# DHJSNoiseConsole.net
KiCad netlist of a schematic drawn in EAGLE
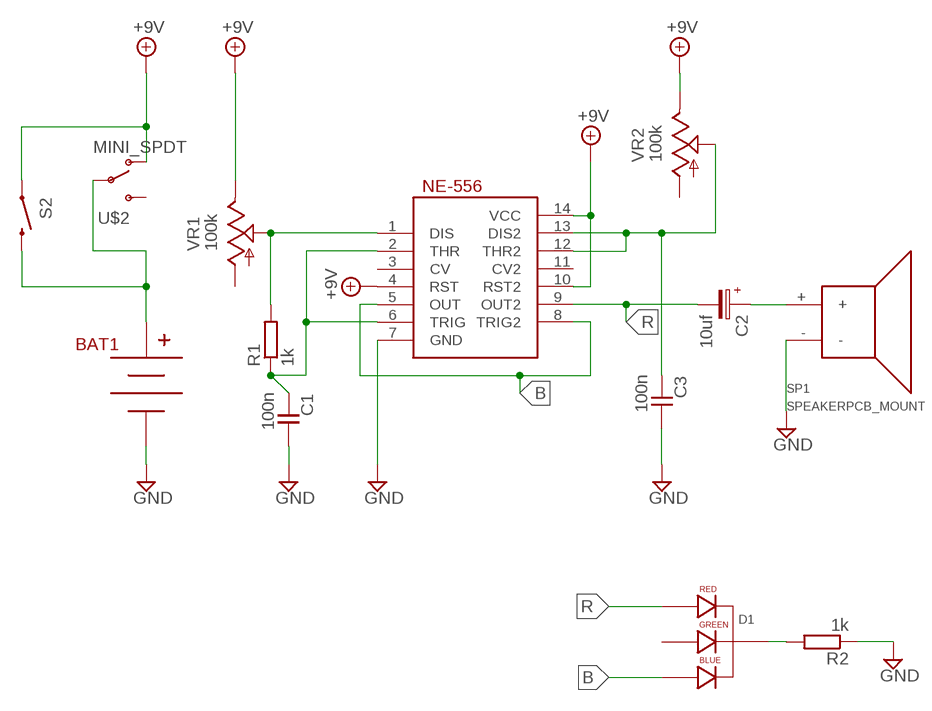
[diagram p0: schematic, sheet 1]

(export (version "E")
  (design (tool "Eeschema 10.0.6"))
  (components
    (comp (ref "BAT1")
      (value "BC9VPC")
      (footprint "eagle-import:BC9VPC")
      (libsource (lib "eagle-import") (part "BC9VPC"))
    )
    (comp (ref "C1")
      (value "100n")
      (footprint "eagle-import:C050-024X044")
      (libsource (lib "eagle-import") (part "C-EU050-024X044"))
    )
    (comp (ref "C2")
      (value "10uf")
      (footprint "eagle-import:050_020")
      (libsource (lib "eagle-import") (part "050-EU"))
    )
    (comp (ref "C3")
      (value "100n")
      (footprint "eagle-import:C050-024X044")
      (libsource (lib "eagle-import") (part "C-EU050-024X044"))
    )
    (comp (ref "D1")
      (value "LED-RGB-CC-THRUCLEAR")
      (footprint "eagle-import:LED-RGB-THRU")
      (libsource (lib "eagle-import") (part "LED-RGB-CC-THRUCLEAR"))
    )
    (comp (ref "NE-556")
      (value "556")
      (footprint "eagle-import:DIL14")
      (libsource (lib "eagle-import") (part "556"))
    )
    (comp (ref "R1")
      (value "1k")
      (footprint "eagle-import:10MM_RESISTOR")
      (libsource (lib "eagle-import") (part "RESISTOR10MM_RESISTOR"))
    )
    (comp (ref "R2")
      (value "1k")
      (footprint "eagle-import:10MM_RESISTOR")
      (libsource (lib "eagle-import") (part "RESISTOR10MM_RESISTOR"))
    )
    (comp (ref "S2")
      (value "SWITCH-MOMENTARY-2SIDE_EZ")
      (footprint "eagle-import:TACTILE-PTH-SIDEEZ")
      (libsource (lib "eagle-import") (part "SWITCH-MOMENTARY-2SIDE_EZ"))
    )
    (comp (ref "SP1")
      (value "SPEAKERPCB_MOUNT")
      (footprint "eagle-import:PCB_MOUNT_SPEAKER")
      (fields (field (name "MFG") "SANCO"))
      (libsource (lib "eagle-import") (part "SPEAKERPCB_MOUNT"))
    )
    (comp (ref "U$2")
      (value "MINI_SPDT")
      (footprint "eagle-import:MINI_SPDT_RIGHTANGLE")
      (libsource (lib "eagle-import") (part "MINI_SPDT"))
    )
    (comp (ref "VR1")
      (value "100k")
      (footprint "eagle-import:9MM_SNAP-IN_POT")
      (libsource (lib "eagle-import") (part "9MM_SNAP-IN_POT_"))
    )
    (comp (ref "VR2")
      (value "100k")
      (footprint "eagle-import:9MM_SNAP-IN_POT")
      (libsource (lib "eagle-import") (part "9MM_SNAP-IN_POT_"))
    )
  )
  (nets
    (net (code "1") (name "+9V") (class "Default")
      (node (ref "NE-556") (pin "10") (pinfunction "RST2_10") (pintype "bidirectional"))
      (node (ref "NE-556") (pin "14") (pinfunction "VCC_14") (pintype "bidirectional"))
      (node (ref "NE-556") (pin "4") (pinfunction "RST_4") (pintype "bidirectional"))
      (node (ref "S2") (pin "1") (pinfunction "1_1") (pintype "passive"))
      (node (ref "U$2") (pin "UP") (pinfunction "O_UP") (pintype "passive"))
      (node (ref "VR1") (pin "3") (pinfunction "E_3") (pintype "passive"))
      (node (ref "VR2") (pin "3") (pinfunction "E_3") (pintype "passive"))
    )
    (net (code "2") (name "B") (class "Default")
      (node (ref "D1") (pin "4") (pinfunction "BLUE_CATHODE_4") (pintype "bidirectional"))
      (node (ref "NE-556") (pin "5") (pinfunction "OUT_5") (pintype "bidirectional"))
      (node (ref "NE-556") (pin "8") (pinfunction "TRIG2_8") (pintype "bidirectional"))
    )
    (net (code "3") (name "GND") (class "Default")
      (node (ref "BAT1") (pin "V-") (pinfunction "V-_V-") (pintype "bidirectional"))
      (node (ref "C1") (pin "1") (pinfunction "1_1") (pintype "passive"))
      (node (ref "C3") (pin "1") (pinfunction "1_1") (pintype "passive"))
      (node (ref "NE-556") (pin "7") (pinfunction "GND_7") (pintype "bidirectional"))
      (node (ref "R2") (pin "1") (pinfunction "1_1") (pintype "passive"))
      (node (ref "SP1") (pin "-") (pinfunction "-_-") (pintype "bidirectional"))
    )
    (net (code "4") (name "Net-(BAT1-PadV+)") (class "Default")
      (node (ref "BAT1") (pin "V+") (pinfunction "V+_V+") (pintype "bidirectional"))
      (node (ref "S2") (pin "2") (pinfunction "2_2") (pintype "passive"))
      (node (ref "U$2") (pin "COMMON") (pinfunction "COMMON_COMMON") (pintype "passive"))
    )
    (net (code "5") (name "Net-(C2-Pad+)") (class "Default")
      (node (ref "C2") (pin "+") (pinfunction "+_+") (pintype "passive"))
      (node (ref "SP1") (pin "+") (pinfunction "+_+") (pintype "bidirectional"))
    )
    (net (code "6") (name "Net-(D1-CATHODE)") (class "Default")
      (node (ref "D1") (pin "2") (pinfunction "CATHODE_2") (pintype "bidirectional"))
      (node (ref "R2") (pin "2") (pinfunction "2_2") (pintype "passive"))
    )
    (net (code "7") (name "Net-(NE-556-DIS)") (class "Default")
      (node (ref "NE-556") (pin "1") (pinfunction "DIS_1") (pintype "bidirectional"))
      (node (ref "R1") (pin "2") (pinfunction "2_2") (pintype "passive"))
      (node (ref "VR1") (pin "2") (pinfunction "S_2") (pintype "passive"))
    )
    (net (code "8") (name "Net-(NE-556-DIS2)") (class "Default")
      (node (ref "C3") (pin "2") (pinfunction "2_2") (pintype "passive"))
      (node (ref "NE-556") (pin "12") (pinfunction "THR2_12") (pintype "bidirectional"))
      (node (ref "NE-556") (pin "13") (pinfunction "DIS2_13") (pintype "bidirectional"))
      (node (ref "VR2") (pin "2") (pinfunction "S_2") (pintype "passive"))
    )
    (net (code "9") (name "Net-(NE-556-THR)") (class "Default")
      (node (ref "C1") (pin "2") (pinfunction "2_2") (pintype "passive"))
      (node (ref "NE-556") (pin "2") (pinfunction "THR_2") (pintype "bidirectional"))
      (node (ref "NE-556") (pin "6") (pinfunction "TRIG_6") (pintype "bidirectional"))
      (node (ref "R1") (pin "1") (pinfunction "1_1") (pintype "passive"))
    )
    (net (code "10") (name "R") (class "Default")
      (node (ref "C2") (pin "-") (pinfunction "-_-") (pintype "passive"))
      (node (ref "D1") (pin "1") (pinfunction "RED_CATHODE_1") (pintype "bidirectional"))
      (node (ref "NE-556") (pin "9") (pinfunction "OUT2_9") (pintype "bidirectional"))
    )
    (net (code "11") (name "unconnected-(D1-GREEN_CATHODE-Pad3)") (class "Default")
      (node (ref "D1") (pin "3") (pinfunction "GREEN_CATHODE_3") (pintype "bidirectional"))
    )
    (net (code "12") (name "unconnected-(NE-556-CV-Pad3)") (class "Default")
      (node (ref "NE-556") (pin "3") (pinfunction "CV_3") (pintype "bidirectional"))
    )
    (net (code "13") (name "unconnected-(NE-556-CV2-Pad11)") (class "Default")
      (node (ref "NE-556") (pin "11") (pinfunction "CV2_11") (pintype "bidirectional"))
    )
    (net (code "14") (name "unconnected-(U$2-S-PadDOWN)") (class "Default")
      (node (ref "U$2") (pin "DOWN") (pinfunction "S_DOWN") (pintype "passive"))
    )
    (net (code "15") (name "unconnected-(VR1-A-Pad1)") (class "Default")
      (node (ref "VR1") (pin "1") (pinfunction "A_1") (pintype "passive"))
    )
    (net (code "16") (name "unconnected-(VR2-A-Pad1)") (class "Default")
      (node (ref "VR2") (pin "1") (pinfunction "A_1") (pintype "passive"))
    )
  )
)
